# controller_board.net
KiCad netlist of a schematic drawn in EAGLE
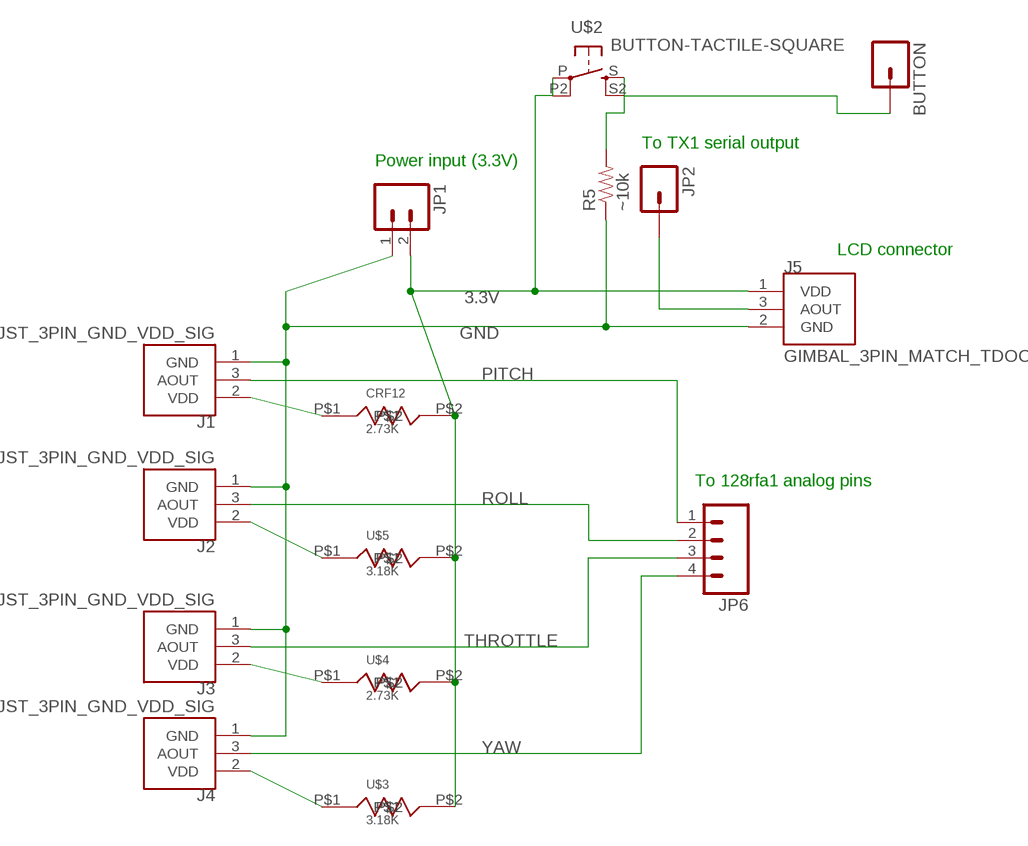
[diagram p0: schematic, sheet 1]

(export (version "E")
  (design (tool "Eeschema 10.0.6"))
  (components
    (comp (ref "BUTTON")
      (value "M01PTH")
      (footprint "eagle-import:1X01")
      (libsource (lib "eagle-import") (part "M01PTH"))
    )
    (comp (ref "CRF12")
      (value "2.73K")
      (footprint "eagle-import:CFR12")
      (libsource (lib "eagle-import") (part "CRF12"))
    )
    (comp (ref "J1")
      (value "JST_3PIN_GND_VDD_SIG")
      (footprint "eagle-import:JST-3-PTH-REVERSE")
      (libsource (lib "eagle-import") (part "JST_3PIN_GND_VDD_SIG"))
    )
    (comp (ref "J2")
      (value "JST_3PIN_GND_VDD_SIG")
      (footprint "eagle-import:JST-3-PTH-REVERSE")
      (libsource (lib "eagle-import") (part "JST_3PIN_GND_VDD_SIG"))
    )
    (comp (ref "J3")
      (value "JST_3PIN_GND_VDD_SIG")
      (footprint "eagle-import:JST-3-PTH-REVERSE")
      (libsource (lib "eagle-import") (part "JST_3PIN_GND_VDD_SIG"))
    )
    (comp (ref "J4")
      (value "JST_3PIN_GND_VDD_SIG")
      (footprint "eagle-import:JST-3-PTH-REVERSE")
      (libsource (lib "eagle-import") (part "JST_3PIN_GND_VDD_SIG"))
    )
    (comp (ref "J5")
      (value "GIMBAL_3PIN_MATCH_TDOCU")
      (footprint "eagle-import:JST-3-PTH")
      (libsource (lib "eagle-import") (part "GIMBAL_3PIN_MATCH_TDOCU"))
    )
    (comp (ref "JP1")
      (value "M021X02_NO_SILK")
      (footprint "eagle-import:1X02_NO_SILK")
      (libsource (lib "eagle-import") (part "M021X02_NO_SILK"))
    )
    (comp (ref "JP2")
      (value "M01PTH")
      (footprint "eagle-import:1X01")
      (libsource (lib "eagle-import") (part "M01PTH"))
    )
    (comp (ref "JP6")
      (value "M04PTH")
      (footprint "eagle-import:1X04")
      (libsource (lib "eagle-import") (part "M04PTH"))
    )
    (comp (ref "R5")
      (value "~10k")
      (footprint "eagle-import:AXIAL-0.4")
      (libsource (lib "eagle-import") (part "RESISTORPTH-1/4W"))
    )
    (comp (ref "U$2")
      (value "BUTTON-TACTILE-SQUARE")
      (footprint "eagle-import:BUTTON-TACTILE-SQUARE-ADAFRUIT1010")
      (libsource (lib "eagle-import") (part "BUTTON-TACTILE-SQUARE"))
    )
    (comp (ref "U$3")
      (value "3.18K")
      (footprint "eagle-import:CFR12")
      (libsource (lib "eagle-import") (part "CRF12"))
    )
    (comp (ref "U$4")
      (value "2.73K")
      (footprint "eagle-import:CFR12")
      (libsource (lib "eagle-import") (part "CRF12"))
    )
    (comp (ref "U$5")
      (value "3.18K")
      (footprint "eagle-import:CFR12")
      (libsource (lib "eagle-import") (part "CRF12"))
    )
  )
  (nets
    (net (code "1") (name "/3.3V") (class "Default")
      (node (ref "CRF12") (pin "P$2") (pinfunction "P$2_P$2") (pintype "bidirectional"))
      (node (ref "J5") (pin "1") (pinfunction "VDD_1") (pintype "power_in"))
      (node (ref "JP1") (pin "2") (pinfunction "2_2") (pintype "passive"))
      (node (ref "U$2") (pin "P") (pinfunction "P_P") (pintype "passive"))
      (node (ref "U$2") (pin "P2") (pinfunction "P1_P2") (pintype "passive"))
      (node (ref "U$3") (pin "P$2") (pinfunction "P$2_P$2") (pintype "bidirectional"))
      (node (ref "U$4") (pin "P$2") (pinfunction "P$2_P$2") (pintype "bidirectional"))
      (node (ref "U$5") (pin "P$2") (pinfunction "P$2_P$2") (pintype "bidirectional"))
    )
    (net (code "2") (name "/GND") (class "Default")
      (node (ref "J1") (pin "1") (pinfunction "GND_1") (pintype "power_in"))
      (node (ref "J2") (pin "1") (pinfunction "GND_1") (pintype "power_in"))
      (node (ref "J3") (pin "1") (pinfunction "GND_1") (pintype "power_in"))
      (node (ref "J4") (pin "1") (pinfunction "GND_1") (pintype "power_in"))
      (node (ref "J5") (pin "2") (pinfunction "GND_2") (pintype "power_in"))
      (node (ref "JP1") (pin "1") (pinfunction "1_1") (pintype "passive"))
      (node (ref "R5") (pin "P$1") (pinfunction "1_P$1") (pintype "passive"))
    )
    (net (code "3") (name "/PITCH") (class "Default")
      (node (ref "J1") (pin "3") (pinfunction "AOUT_3") (pintype "bidirectional"))
      (node (ref "JP6") (pin "1") (pinfunction "1_1") (pintype "passive"))
    )
    (net (code "4") (name "/ROLL") (class "Default")
      (node (ref "J2") (pin "3") (pinfunction "AOUT_3") (pintype "bidirectional"))
      (node (ref "JP6") (pin "2") (pinfunction "2_2") (pintype "passive"))
    )
    (net (code "5") (name "/THROTTLE") (class "Default")
      (node (ref "J3") (pin "3") (pinfunction "AOUT_3") (pintype "bidirectional"))
      (node (ref "JP6") (pin "3") (pinfunction "3_3") (pintype "passive"))
    )
    (net (code "6") (name "/YAW") (class "Default")
      (node (ref "J4") (pin "3") (pinfunction "AOUT_3") (pintype "bidirectional"))
      (node (ref "JP6") (pin "4") (pinfunction "4_4") (pintype "passive"))
    )
    (net (code "7") (name "Net-(J1-VDD)") (class "Default")
      (node (ref "CRF12") (pin "P$1") (pinfunction "P$1_P$1") (pintype "bidirectional"))
      (node (ref "J1") (pin "2") (pinfunction "VDD_2") (pintype "power_in"))
    )
    (net (code "8") (name "Net-(J2-VDD)") (class "Default")
      (node (ref "J2") (pin "2") (pinfunction "VDD_2") (pintype "power_in"))
      (node (ref "U$5") (pin "P$1") (pinfunction "P$1_P$1") (pintype "bidirectional"))
    )
    (net (code "9") (name "Net-(J3-VDD)") (class "Default")
      (node (ref "J3") (pin "2") (pinfunction "VDD_2") (pintype "power_in"))
      (node (ref "U$4") (pin "P$1") (pinfunction "P$1_P$1") (pintype "bidirectional"))
    )
    (net (code "10") (name "Net-(J4-VDD)") (class "Default")
      (node (ref "J4") (pin "2") (pinfunction "VDD_2") (pintype "power_in"))
      (node (ref "U$3") (pin "P$1") (pinfunction "P$1_P$1") (pintype "bidirectional"))
    )
    (net (code "11") (name "Net-(J5-AOUT)") (class "Default")
      (node (ref "J5") (pin "3") (pinfunction "AOUT_3") (pintype "bidirectional"))
      (node (ref "JP2") (pin "1") (pinfunction "1_1") (pintype "passive"))
    )
    (net (code "12") (name "Net-(R5-2)") (class "Default")
      (node (ref "BUTTON") (pin "1") (pinfunction "1_1") (pintype "passive"))
      (node (ref "R5") (pin "P$2") (pinfunction "2_P$2") (pintype "passive"))
      (node (ref "U$2") (pin "S") (pinfunction "S_S") (pintype "passive"))
      (node (ref "U$2") (pin "S2") (pinfunction "S1_S2") (pintype "passive"))
    )
  )
)
